# Logic_board.net
KiCad netlist of a schematic drawn in EAGLE
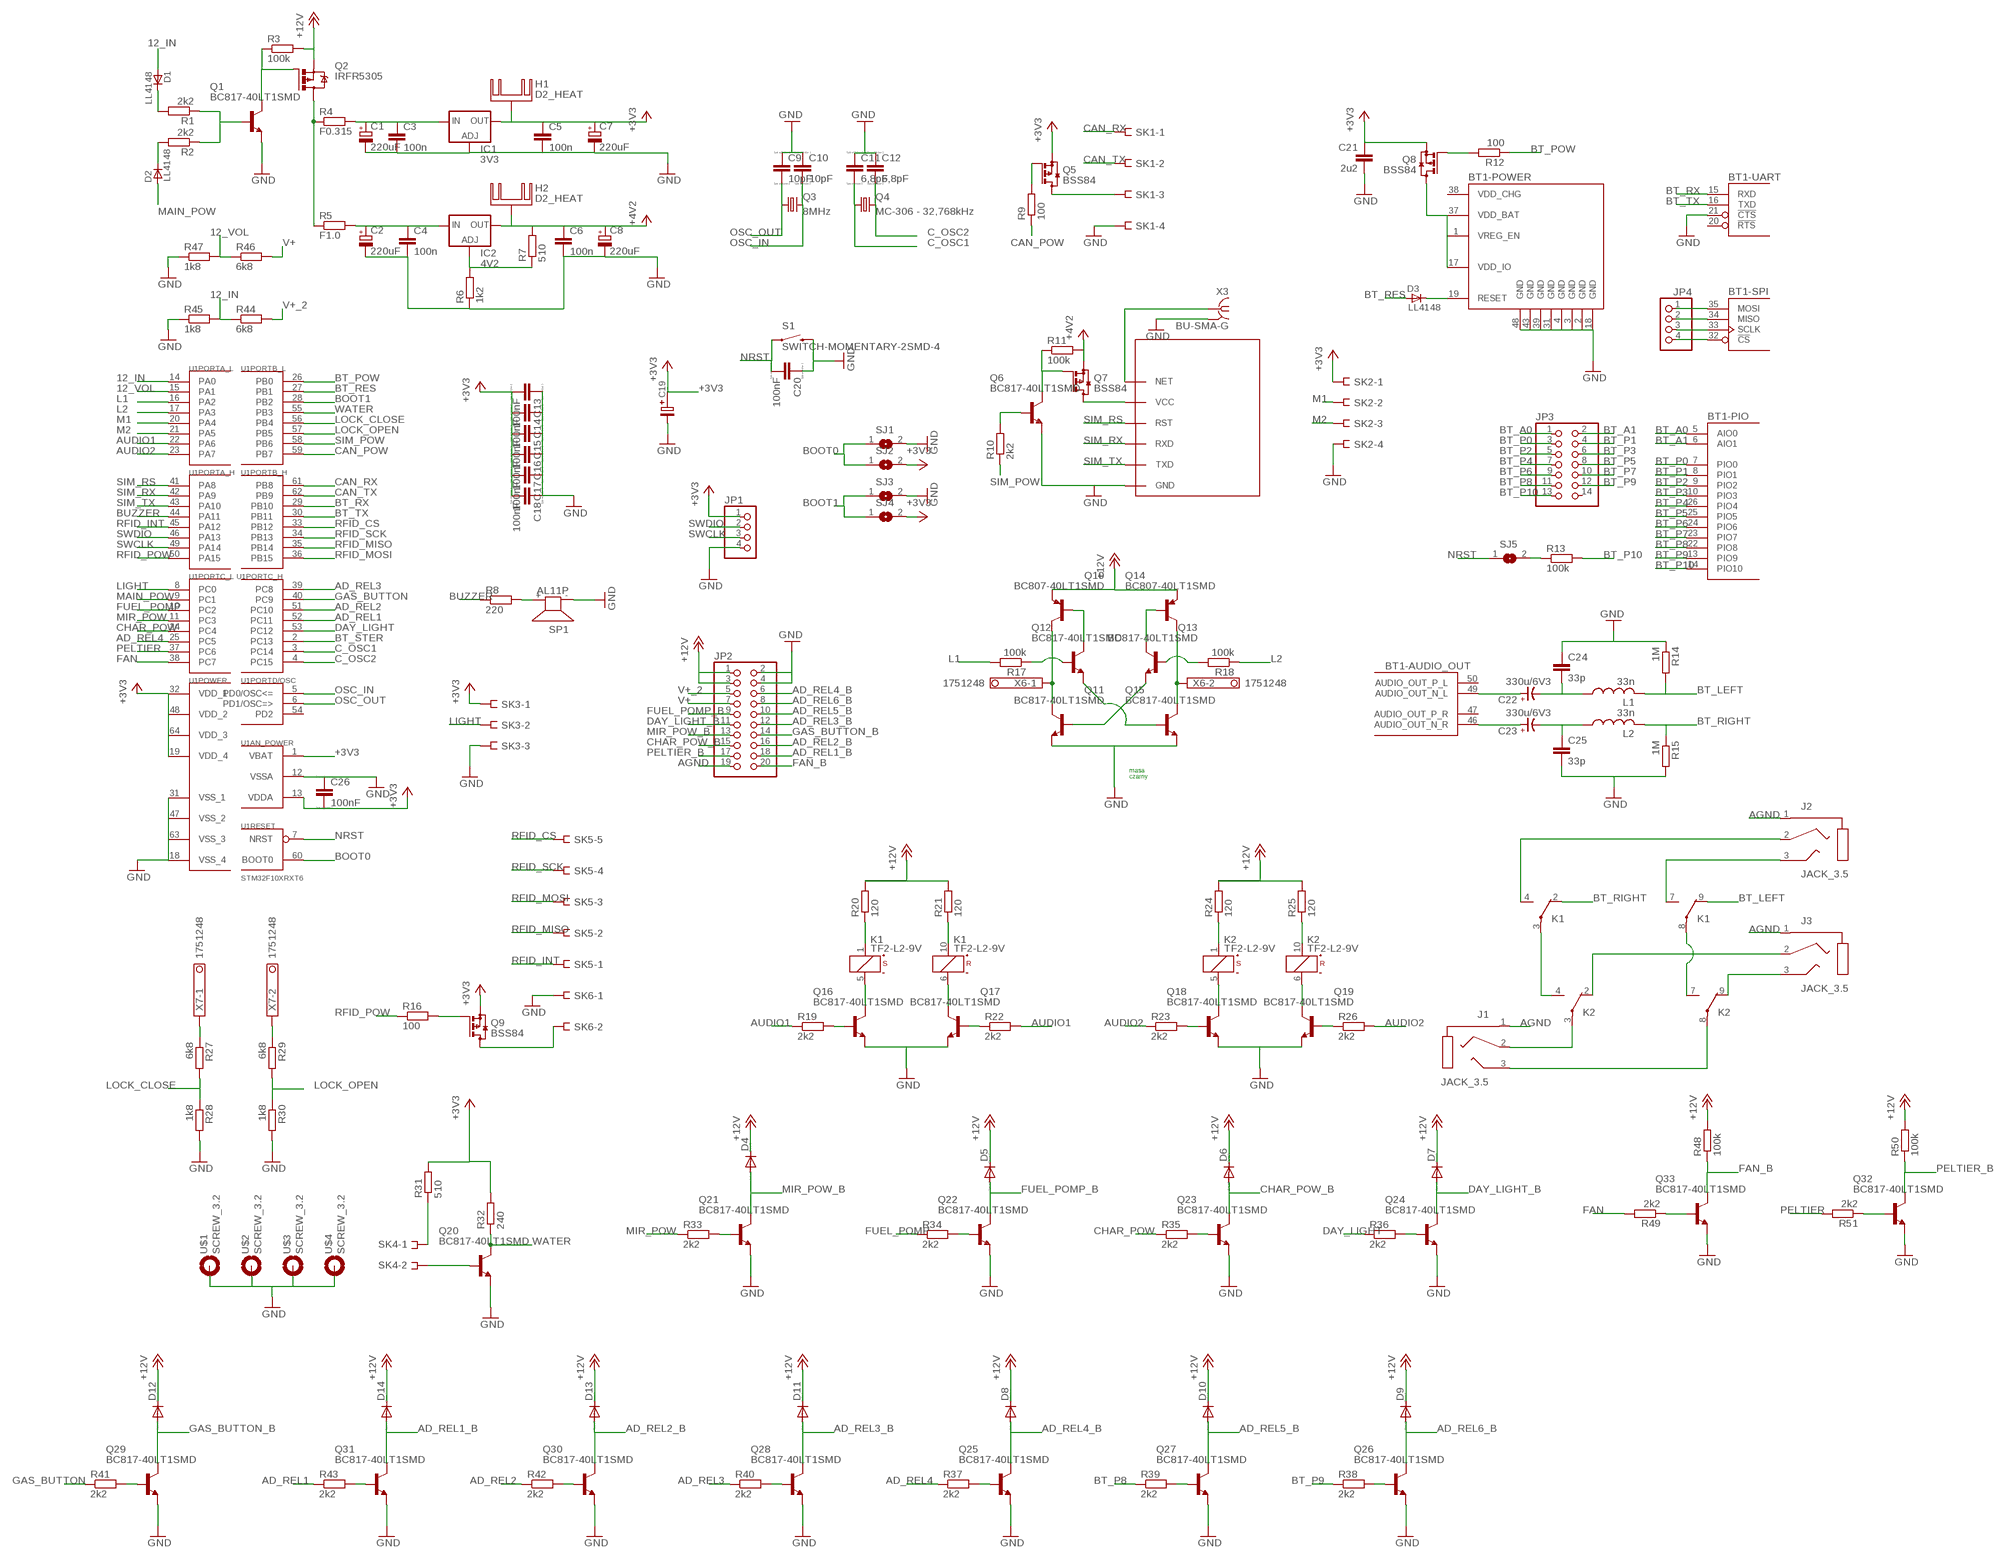
[diagram p0: schematic, sheet 1]

(export (version "E")
  (design (tool "Eeschema 10.0.6"))
  (components
    (comp (ref "BT1")
      (value "WT32I")
      (footprint "eagle-import:WT32I")
      (libsource (lib "eagle-import") (part "WT32I"))
    )
    (comp (ref "C1")
      (value "220uF")
      (footprint "eagle-import:PANASONIC_D")
      (libsource (lib "eagle-import") (part "CPOL-EUD"))
    )
    (comp (ref "C2")
      (value "220uF")
      (footprint "eagle-import:PANASONIC_D")
      (libsource (lib "eagle-import") (part "CPOL-EUD"))
    )
    (comp (ref "C3")
      (value "100n")
      (footprint "eagle-import:C2012")
      (libsource (lib "eagle-import") (part "C-EUC2012"))
    )
    (comp (ref "C4")
      (value "100n")
      (footprint "eagle-import:C2012")
      (libsource (lib "eagle-import") (part "C-EUC2012"))
    )
    (comp (ref "C5")
      (value "100n")
      (footprint "eagle-import:C2012")
      (libsource (lib "eagle-import") (part "C-EUC2012"))
    )
    (comp (ref "C6")
      (value "100n")
      (footprint "eagle-import:C2012")
      (libsource (lib "eagle-import") (part "C-EUC2012"))
    )
    (comp (ref "C7")
      (value "220uF")
      (footprint "eagle-import:PANASONIC_D")
      (libsource (lib "eagle-import") (part "CPOL-EUD"))
    )
    (comp (ref "C8")
      (value "220uF")
      (footprint "eagle-import:PANASONIC_D")
      (libsource (lib "eagle-import") (part "CPOL-EUD"))
    )
    (comp (ref "C9")
      (value "10pF")
      (footprint "eagle-import:C2012")
      (libsource (lib "eagle-import") (part "CC2012"))
    )
    (comp (ref "C10")
      (value "10pF")
      (footprint "eagle-import:C2012")
      (libsource (lib "eagle-import") (part "CC2012"))
    )
    (comp (ref "C11")
      (value "6,8pF")
      (footprint "eagle-import:C2012")
      (libsource (lib "eagle-import") (part "CC2012"))
    )
    (comp (ref "C12")
      (value "6,8pF")
      (footprint "eagle-import:C2012")
      (libsource (lib "eagle-import") (part "CC2012"))
    )
    (comp (ref "C13")
      (value "100nF")
      (footprint "eagle-import:C2012")
      (libsource (lib "eagle-import") (part "CC2012"))
    )
    (comp (ref "C14")
      (value "100nF")
      (footprint "eagle-import:C2012")
      (libsource (lib "eagle-import") (part "CC2012"))
    )
    (comp (ref "C15")
      (value "100nF")
      (footprint "eagle-import:C2012")
      (libsource (lib "eagle-import") (part "CC2012"))
    )
    (comp (ref "C16")
      (value "100nF")
      (footprint "eagle-import:C2012")
      (libsource (lib "eagle-import") (part "CC2012"))
    )
    (comp (ref "C17")
      (value "100nF")
      (footprint "eagle-import:C2012")
      (libsource (lib "eagle-import") (part "CC2012"))
    )
    (comp (ref "C18")
      (value "100nF")
      (footprint "eagle-import:C2012")
      (libsource (lib "eagle-import") (part "CC2012"))
    )
    (comp (ref "C19")
      (value "CAP-13,5")
      (footprint "eagle-import:PAC-G-1")
      (libsource (lib "eagle-import") (part "CAP-13,5"))
    )
    (comp (ref "C20")
      (value "100nF")
      (footprint "eagle-import:C2012")
      (libsource (lib "eagle-import") (part "CC2012"))
    )
    (comp (ref "C21")
      (value "2u2")
      (footprint "eagle-import:C2012")
      (libsource (lib "eagle-import") (part "C-EUC2012"))
    )
    (comp (ref "C22")
      (value "330u/6V3")
      (footprint "eagle-import:7343_T")
      (libsource (lib "eagle-import") (part "CP-7343"))
    )
    (comp (ref "C23")
      (value "330u/6V3")
      (footprint "eagle-import:7343_T")
      (libsource (lib "eagle-import") (part "CP-7343"))
    )
    (comp (ref "C24")
      (value "33p")
      (footprint "eagle-import:C2012")
      (libsource (lib "eagle-import") (part "C-EUC2012"))
    )
    (comp (ref "C25")
      (value "33p")
      (footprint "eagle-import:C2012")
      (libsource (lib "eagle-import") (part "C-EUC2012"))
    )
    (comp (ref "C26")
      (value "100nF")
      (footprint "eagle-import:C2012")
      (libsource (lib "eagle-import") (part "CC2012"))
    )
    (comp (ref "D1")
      (value "LL4148")
      (footprint "eagle-import:SOD80_DO213AA_MINIMELF")
      (libsource (lib "eagle-import") (part "LL4148"))
    )
    (comp (ref "D2")
      (value "LL4148")
      (footprint "eagle-import:SOD80_DO213AA_MINIMELF")
      (libsource (lib "eagle-import") (part "LL4148"))
    )
    (comp (ref "D3")
      (value "LL4148")
      (footprint "eagle-import:SOD80_DO213AA_MINIMELF")
      (libsource (lib "eagle-import") (part "LL4148"))
    )
    (comp (ref "D4")
      (value "DIODE-DO-214AC")
      (footprint "eagle-import:DO-214AC")
      (libsource (lib "eagle-import") (part "DIODE-DO-214AC"))
    )
    (comp (ref "D5")
      (value "DIODE-DO-214AC")
      (footprint "eagle-import:DO-214AC")
      (libsource (lib "eagle-import") (part "DIODE-DO-214AC"))
    )
    (comp (ref "D6")
      (value "DIODE-DO-214AC")
      (footprint "eagle-import:DO-214AC")
      (libsource (lib "eagle-import") (part "DIODE-DO-214AC"))
    )
    (comp (ref "D7")
      (value "DIODE-DO-214AC")
      (footprint "eagle-import:DO-214AC")
      (libsource (lib "eagle-import") (part "DIODE-DO-214AC"))
    )
    (comp (ref "D8")
      (value "DIODE-DO-214AC")
      (footprint "eagle-import:DO-214AC")
      (libsource (lib "eagle-import") (part "DIODE-DO-214AC"))
    )
    (comp (ref "D9")
      (value "DIODE-DO-214AC")
      (footprint "eagle-import:DO-214AC")
      (libsource (lib "eagle-import") (part "DIODE-DO-214AC"))
    )
    (comp (ref "D10")
      (value "DIODE-DO-214AC")
      (footprint "eagle-import:DO-214AC")
      (libsource (lib "eagle-import") (part "DIODE-DO-214AC"))
    )
    (comp (ref "D11")
      (value "DIODE-DO-214AC")
      (footprint "eagle-import:DO-214AC")
      (libsource (lib "eagle-import") (part "DIODE-DO-214AC"))
    )
    (comp (ref "D12")
      (value "DIODE-DO-214AC")
      (footprint "eagle-import:DO-214AC")
      (libsource (lib "eagle-import") (part "DIODE-DO-214AC"))
    )
    (comp (ref "D13")
      (value "DIODE-DO-214AC")
      (footprint "eagle-import:DO-214AC")
      (libsource (lib "eagle-import") (part "DIODE-DO-214AC"))
    )
    (comp (ref "D14")
      (value "DIODE-DO-214AC")
      (footprint "eagle-import:DO-214AC")
      (libsource (lib "eagle-import") (part "DIODE-DO-214AC"))
    )
    (comp (ref "H1")
      (value "D2_HEAT")
      (footprint "eagle-import:D2PACK_HEATSINK")
      (libsource (lib "eagle-import") (part "D2_HEAT"))
    )
    (comp (ref "H2")
      (value "D2_HEAT")
      (footprint "eagle-import:D2PACK_HEATSINK")
      (libsource (lib "eagle-import") (part "D2_HEAT"))
    )
    (comp (ref "IC1")
      (value "3V3")
      (footprint "eagle-import:D2PACK")
      (libsource (lib "eagle-import") (part "LM317?BD2T"))
    )
    (comp (ref "IC2")
      (value "4V2")
      (footprint "eagle-import:D2PACK")
      (libsource (lib "eagle-import") (part "LM317?BD2T"))
    )
    (comp (ref "J1")
      (value "JACK_3.5")
      (footprint "eagle-import:STX3100")
      (libsource (lib "eagle-import") (part "JACK_3.5"))
    )
    (comp (ref "J2")
      (value "JACK_3.5")
      (footprint "eagle-import:STX3100")
      (libsource (lib "eagle-import") (part "JACK_3.5"))
    )
    (comp (ref "J3")
      (value "JACK_3.5")
      (footprint "eagle-import:STX3100")
      (libsource (lib "eagle-import") (part "JACK_3.5"))
    )
    (comp (ref "JP1")
      (value "PINHD-1X4")
      (footprint "eagle-import:1X04")
      (libsource (lib "eagle-import") (part "PINHD-1X4"))
    )
    (comp (ref "JP2")
      (value "PINHD-2X10")
      (footprint "eagle-import:2X10")
      (libsource (lib "eagle-import") (part "PINHD-2X10"))
    )
    (comp (ref "JP3")
      (value "PINHD-2X7")
      (footprint "eagle-import:2X07")
      (libsource (lib "eagle-import") (part "PINHD-2X7"))
    )
    (comp (ref "JP4")
      (value "PINHD-1X4")
      (footprint "eagle-import:1X04")
      (libsource (lib "eagle-import") (part "PINHD-1X4"))
    )
    (comp (ref "K1")
      (value "TF2-L2-9V")
      (footprint "eagle-import:TF2")
      (libsource (lib "eagle-import") (part "TF2-L2-9V"))
    )
    (comp (ref "K2")
      (value "TF2-L2-9V")
      (footprint "eagle-import:TF2")
      (libsource (lib "eagle-import") (part "TF2-L2-9V"))
    )
    (comp (ref "L1")
      (value "33n")
      (footprint "eagle-import:L2012C")
      (libsource (lib "eagle-import") (part "L-USL2012C"))
    )
    (comp (ref "L2")
      (value "33n")
      (footprint "eagle-import:L2012C")
      (libsource (lib "eagle-import") (part "L-USL2012C"))
    )
    (comp (ref "Q1")
      (value "BC817-40LT1SMD")
      (footprint "eagle-import:SOT23-BEC")
      (libsource (lib "eagle-import") (part "BC817SMD-40LT1"))
    )
    (comp (ref "Q2")
      (value "IRFR5305")
      (footprint "eagle-import:D-PAK_TO252AA")
      (libsource (lib "eagle-import") (part "IRF?5305R"))
    )
    (comp (ref "Q3")
      (value "8MHz")
      (footprint "eagle-import:HC49UP")
      (libsource (lib "eagle-import") (part "CRYSTALHC49UP"))
    )
    (comp (ref "Q4")
      (value "MC-306 - 32,768kHz")
      (footprint "eagle-import:MC-306")
      (fields (field (name "MPN") "MC-306 60.0KHZ  100PPM ,12.5PF"))
      (libsource (lib "eagle-import") (part "MC-306"))
    )
    (comp (ref "Q5")
      (value "BSS84")
      (footprint "eagle-import:SOT23")
      (libsource (lib "eagle-import") (part "BSS84"))
    )
    (comp (ref "Q6")
      (value "BC817-40LT1SMD")
      (footprint "eagle-import:SOT23-BEC")
      (libsource (lib "eagle-import") (part "BC817SMD-40LT1"))
    )
    (comp (ref "Q7")
      (value "BSS84")
      (footprint "eagle-import:SOT23")
      (libsource (lib "eagle-import") (part "BSS84"))
    )
    (comp (ref "Q8")
      (value "BSS84")
      (footprint "eagle-import:SOT23")
      (libsource (lib "eagle-import") (part "BSS84"))
    )
    (comp (ref "Q9")
      (value "BSS84")
      (footprint "eagle-import:SOT23")
      (libsource (lib "eagle-import") (part "BSS84"))
    )
    (comp (ref "Q10")
      (value "BC807-40LT1SMD")
      (footprint "eagle-import:SOT23-BEC")
      (libsource (lib "eagle-import") (part "BC807SMD-40LT1"))
    )
    (comp (ref "Q11")
      (value "BC817-40LT1SMD")
      (footprint "eagle-import:SOT23-BEC")
      (libsource (lib "eagle-import") (part "BC817SMD-40LT1"))
    )
    (comp (ref "Q12")
      (value "BC817-40LT1SMD")
      (footprint "eagle-import:SOT23-BEC")
      (libsource (lib "eagle-import") (part "BC817SMD-40LT1"))
    )
    (comp (ref "Q13")
      (value "BC817-40LT1SMD")
      (footprint "eagle-import:SOT23-BEC")
      (libsource (lib "eagle-import") (part "BC817SMD-40LT1"))
    )
    (comp (ref "Q14")
      (value "BC807-40LT1SMD")
      (footprint "eagle-import:SOT23-BEC")
      (libsource (lib "eagle-import") (part "BC807SMD-40LT1"))
    )
    (comp (ref "Q15")
      (value "BC817-40LT1SMD")
      (footprint "eagle-import:SOT23-BEC")
      (libsource (lib "eagle-import") (part "BC817SMD-40LT1"))
    )
    (comp (ref "Q16")
      (value "BC817-40LT1SMD")
      (footprint "eagle-import:SOT23-BEC")
      (libsource (lib "eagle-import") (part "BC817SMD-40LT1"))
    )
    (comp (ref "Q17")
      (value "BC817-40LT1SMD")
      (footprint "eagle-import:SOT23-BEC")
      (libsource (lib "eagle-import") (part "BC817SMD-40LT1"))
    )
    (comp (ref "Q18")
      (value "BC817-40LT1SMD")
      (footprint "eagle-import:SOT23-BEC")
      (libsource (lib "eagle-import") (part "BC817SMD-40LT1"))
    )
    (comp (ref "Q19")
      (value "BC817-40LT1SMD")
      (footprint "eagle-import:SOT23-BEC")
      (libsource (lib "eagle-import") (part "BC817SMD-40LT1"))
    )
    (comp (ref "Q20")
      (value "BC817-40LT1SMD")
      (footprint "eagle-import:SOT23-BEC")
      (libsource (lib "eagle-import") (part "BC817SMD-40LT1"))
    )
    (comp (ref "Q21")
      (value "BC817-40LT1SMD")
      (footprint "eagle-import:SOT23-BEC")
      (libsource (lib "eagle-import") (part "BC817SMD-40LT1"))
    )
    (comp (ref "Q22")
      (value "BC817-40LT1SMD")
      (footprint "eagle-import:SOT23-BEC")
      (libsource (lib "eagle-import") (part "BC817SMD-40LT1"))
    )
    (comp (ref "Q23")
      (value "BC817-40LT1SMD")
      (footprint "eagle-import:SOT23-BEC")
      (libsource (lib "eagle-import") (part "BC817SMD-40LT1"))
    )
    (comp (ref "Q24")
      (value "BC817-40LT1SMD")
      (footprint "eagle-import:SOT23-BEC")
      (libsource (lib "eagle-import") (part "BC817SMD-40LT1"))
    )
    (comp (ref "Q25")
      (value "BC817-40LT1SMD")
      (footprint "eagle-import:SOT23-BEC")
      (libsource (lib "eagle-import") (part "BC817SMD-40LT1"))
    )
    (comp (ref "Q26")
      (value "BC817-40LT1SMD")
      (footprint "eagle-import:SOT23-BEC")
      (libsource (lib "eagle-import") (part "BC817SMD-40LT1"))
    )
    (comp (ref "Q27")
      (value "BC817-40LT1SMD")
      (footprint "eagle-import:SOT23-BEC")
      (libsource (lib "eagle-import") (part "BC817SMD-40LT1"))
    )
    (comp (ref "Q28")
      (value "BC817-40LT1SMD")
      (footprint "eagle-import:SOT23-BEC")
      (libsource (lib "eagle-import") (part "BC817SMD-40LT1"))
    )
    (comp (ref "Q29")
      (value "BC817-40LT1SMD")
      (footprint "eagle-import:SOT23-BEC")
      (libsource (lib "eagle-import") (part "BC817SMD-40LT1"))
    )
    (comp (ref "Q30")
      (value "BC817-40LT1SMD")
      (footprint "eagle-import:SOT23-BEC")
      (libsource (lib "eagle-import") (part "BC817SMD-40LT1"))
    )
    (comp (ref "Q31")
      (value "BC817-40LT1SMD")
      (footprint "eagle-import:SOT23-BEC")
      (libsource (lib "eagle-import") (part "BC817SMD-40LT1"))
    )
    (comp (ref "Q32")
      (value "BC817-40LT1SMD")
      (footprint "eagle-import:SOT23-BEC")
      (libsource (lib "eagle-import") (part "BC817SMD-40LT1"))
    )
    (comp (ref "Q33")
      (value "BC817-40LT1SMD")
      (footprint "eagle-import:SOT23-BEC")
      (libsource (lib "eagle-import") (part "BC817SMD-40LT1"))
    )
    (comp (ref "R1")
      (value "2k2")
      (footprint "eagle-import:R0805")
      (libsource (lib "eagle-import") (part "R-EU_R0805"))
    )
    (comp (ref "R2")
      (value "2k2")
      (footprint "eagle-import:R0805")
      (libsource (lib "eagle-import") (part "R-EU_R0805"))
    )
    (comp (ref "R3")
      (value "100k")
      (footprint "eagle-import:R0805")
      (libsource (lib "eagle-import") (part "R-EU_R0805"))
    )
    (comp (ref "R4")
      (value "F0.315")
      (footprint "eagle-import:R2512")
      (libsource (lib "eagle-import") (part "R-EU_R2512"))
    )
    (comp (ref "R5")
      (value "F1.0")
      (footprint "eagle-import:R2512")
      (libsource (lib "eagle-import") (part "R-EU_R2512"))
    )
    (comp (ref "R6")
      (value "1k2")
      (footprint "eagle-import:R0805")
      (libsource (lib "eagle-import") (part "R-EU_R0805"))
    )
    (comp (ref "R7")
      (value "510")
      (footprint "eagle-import:R0805")
      (libsource (lib "eagle-import") (part "R-EU_R0805"))
    )
    (comp (ref "R8")
      (value "220")
      (footprint "eagle-import:R0805")
      (libsource (lib "eagle-import") (part "R-EU_R0805"))
    )
    (comp (ref "R9")
      (value "100")
      (footprint "eagle-import:R0805")
      (libsource (lib "eagle-import") (part "R-EU_R0805"))
    )
    (comp (ref "R10")
      (value "2k2")
      (footprint "eagle-import:R0805")
      (libsource (lib "eagle-import") (part "R-EU_R0805"))
    )
    (comp (ref "R11")
      (value "100k")
      (footprint "eagle-import:R0805")
      (libsource (lib "eagle-import") (part "R-EU_R0805"))
    )
    (comp (ref "R12")
      (value "100")
      (footprint "eagle-import:R0805")
      (libsource (lib "eagle-import") (part "R-EU_R0805"))
    )
    (comp (ref "R13")
      (value "100k")
      (footprint "eagle-import:R0805")
      (libsource (lib "eagle-import") (part "R-EU_R0805"))
    )
    (comp (ref "R14")
      (value "1M")
      (footprint "eagle-import:R0805")
      (libsource (lib "eagle-import") (part "R-EU_R0805"))
    )
    (comp (ref "R15")
      (value "1M")
      (footprint "eagle-import:R0805")
      (libsource (lib "eagle-import") (part "R-EU_R0805"))
    )
    (comp (ref "R16")
      (value "100")
      (footprint "eagle-import:R0805")
      (libsource (lib "eagle-import") (part "R-EU_R0805"))
    )
    (comp (ref "R17")
      (value "100k")
      (footprint "eagle-import:R0805")
      (libsource (lib "eagle-import") (part "R-EU_R0805"))
    )
    (comp (ref "R18")
      (value "100k")
      (footprint "eagle-import:R0805")
      (libsource (lib "eagle-import") (part "R-EU_R0805"))
    )
    (comp (ref "R19")
      (value "2k2")
      (footprint "eagle-import:R0805")
      (libsource (lib "eagle-import") (part "R-EU_R0805"))
    )
    (comp (ref "R20")
      (value "120")
      (footprint "eagle-import:R0805")
      (libsource (lib "eagle-import") (part "R-EU_R0805"))
    )
    (comp (ref "R21")
      (value "120")
      (footprint "eagle-import:R0805")
      (libsource (lib "eagle-import") (part "R-EU_R0805"))
    )
    (comp (ref "R22")
      (value "2k2")
      (footprint "eagle-import:R0805")
      (libsource (lib "eagle-import") (part "R-EU_R0805"))
    )
    (comp (ref "R23")
      (value "2k2")
      (footprint "eagle-import:R0805")
      (libsource (lib "eagle-import") (part "R-EU_R0805"))
    )
    (comp (ref "R24")
      (value "120")
      (footprint "eagle-import:R0805")
      (libsource (lib "eagle-import") (part "R-EU_R0805"))
    )
    (comp (ref "R25")
      (value "120")
      (footprint "eagle-import:R0805")
      (libsource (lib "eagle-import") (part "R-EU_R0805"))
    )
    (comp (ref "R26")
      (value "2k2")
      (footprint "eagle-import:R0805")
      (libsource (lib "eagle-import") (part "R-EU_R0805"))
    )
    (comp (ref "R27")
      (value "6k8")
      (footprint "eagle-import:R0805")
      (libsource (lib "eagle-import") (part "R-EU_R0805"))
    )
    (comp (ref "R28")
      (value "1k8")
      (footprint "eagle-import:R0805")
      (libsource (lib "eagle-import") (part "R-EU_R0805"))
    )
    (comp (ref "R29")
      (value "6k8")
      (footprint "eagle-import:R0805")
      (libsource (lib "eagle-import") (part "R-EU_R0805"))
    )
    (comp (ref "R30")
      (value "1k8")
      (footprint "eagle-import:R0805")
      (libsource (lib "eagle-import") (part "R-EU_R0805"))
    )
    (comp (ref "R31")
      (value "510")
      (footprint "eagle-import:R0805")
      (libsource (lib "eagle-import") (part "R-EU_R0805"))
    )
    (comp (ref "R32")
      (value "240")
      (footprint "eagle-import:R0805")
      (libsource (lib "eagle-import") (part "R-EU_R0805"))
    )
    (comp (ref "R33")
      (value "2k2")
      (footprint "eagle-import:R0805")
      (libsource (lib "eagle-import") (part "R-EU_R0805"))
    )
    (comp (ref "R34")
      (value "2k2")
      (footprint "eagle-import:R0805")
      (libsource (lib "eagle-import") (part "R-EU_R0805"))
    )
    (comp (ref "R35")
      (value "2k2")
      (footprint "eagle-import:R0805")
      (libsource (lib "eagle-import") (part "R-EU_R0805"))
    )
    (comp (ref "R36")
      (value "2k2")
      (footprint "eagle-import:R0805")
      (libsource (lib "eagle-import") (part "R-EU_R0805"))
    )
    (comp (ref "R37")
      (value "2k2")
      (footprint "eagle-import:R0805")
      (libsource (lib "eagle-import") (part "R-EU_R0805"))
    )
    (comp (ref "R38")
      (value "2k2")
      (footprint "eagle-import:R0805")
      (libsource (lib "eagle-import") (part "R-EU_R0805"))
    )
    (comp (ref "R39")
      (value "2k2")
      (footprint "eagle-import:R0805")
      (libsource (lib "eagle-import") (part "R-EU_R0805"))
    )
    (comp (ref "R40")
      (value "2k2")
      (footprint "eagle-import:R0805")
      (libsource (lib "eagle-import") (part "R-EU_R0805"))
    )
    (comp (ref "R41")
      (value "2k2")
      (footprint "eagle-import:R0805")
      (libsource (lib "eagle-import") (part "R-EU_R0805"))
    )
    (comp (ref "R42")
      (value "2k2")
      (footprint "eagle-import:R0805")
      (libsource (lib "eagle-import") (part "R-EU_R0805"))
    )
    (comp (ref "R43")
      (value "2k2")
      (footprint "eagle-import:R0805")
      (libsource (lib "eagle-import") (part "R-EU_R0805"))
    )
    (comp (ref "R44")
      (value "6k8")
      (footprint "eagle-import:R0805")
      (libsource (lib "eagle-import") (part "R-EU_R0805"))
    )
    (comp (ref "R45")
      (value "1k8")
      (footprint "eagle-import:R0805")
      (libsource (lib "eagle-import") (part "R-EU_R0805"))
    )
    (comp (ref "R46")
      (value "6k8")
      (footprint "eagle-import:R0805")
      (libsource (lib "eagle-import") (part "R-EU_R0805"))
    )
    (comp (ref "R47")
      (value "1k8")
      (footprint "eagle-import:R0805")
      (libsource (lib "eagle-import") (part "R-EU_R0805"))
    )
    (comp (ref "R48")
      (value "100k")
      (footprint "eagle-import:R0805")
      (libsource (lib "eagle-import") (part "R-EU_R0805"))
    )
    (comp (ref "R49")
      (value "2k2")
      (footprint "eagle-import:R0805")
      (libsource (lib "eagle-import") (part "R-EU_R0805"))
    )
    (comp (ref "R50")
      (value "100k")
      (footprint "eagle-import:R0805")
      (libsource (lib "eagle-import") (part "R-EU_R0805"))
    )
    (comp (ref "R51")
      (value "2k2")
      (footprint "eagle-import:R0805")
      (libsource (lib "eagle-import") (part "R-EU_R0805"))
    )
    (comp (ref "S1")
      (value "SWITCH-MOMENTARY-2SMD-4")
      (footprint "eagle-import:TACTILE_SWITCH_TALL")
      (libsource (lib "eagle-import") (part "SWITCH-MOMENTARY-2SMD-4"))
    )
    (comp (ref "SJ1") (value "SJ") (footprint "eagle-import:SJ") (libsource (lib "eagle-import") (part "SJ")))
    (comp (ref "SJ2") (value "SJ") (footprint "eagle-import:SJ") (libsource (lib "eagle-import") (part "SJ")))
    (comp (ref "SJ3") (value "SJ") (footprint "eagle-import:SJ") (libsource (lib "eagle-import") (part "SJ")))
    (comp (ref "SJ4") (value "SJ") (footprint "eagle-import:SJ") (libsource (lib "eagle-import") (part "SJ")))
    (comp (ref "SJ5") (value "SJ") (footprint "eagle-import:SJ") (libsource (lib "eagle-import") (part "SJ")))
    (comp (ref "SK1")
      (value "DF3-04S")
      (footprint "eagle-import:DF3S-04")
      (libsource (lib "eagle-import") (part "DF3-04S"))
    )
    (comp (ref "SK2")
      (value "DF3-04S")
      (footprint "eagle-import:DF3S-04")
      (libsource (lib "eagle-import") (part "DF3-04S"))
    )
    (comp (ref "SK3")
      (value "DF3-03S")
      (footprint "eagle-import:DF3S-03")
      (libsource (lib "eagle-import") (part "DF3-03S"))
    )
    (comp (ref "SK4")
      (value "DF3-02S")
      (footprint "eagle-import:DF3S-02")
      (libsource (lib "eagle-import") (part "DF3-02S"))
    )
    (comp (ref "SK5")
      (value "DF3-05S")
      (footprint "eagle-import:DF3S-05")
      (libsource (lib "eagle-import") (part "DF3-05S"))
    )
    (comp (ref "SK6")
      (value "DF3-02S")
      (footprint "eagle-import:DF3S-02")
      (libsource (lib "eagle-import") (part "DF3-02S"))
    )
    (comp (ref "SP1")
      (value "AL11P")
      (footprint "eagle-import:AL11P")
      (libsource (lib "eagle-import") (part "AL11P"))
    )
    (comp (ref "U$1")
      (value "SCREW_3.2")
      (footprint "eagle-import:3,2-PAD")
      (libsource (lib "eagle-import") (part "SCREW_3.2"))
    )
    (comp (ref "U$2")
      (value "SCREW_3.2")
      (footprint "eagle-import:3,2-PAD")
      (libsource (lib "eagle-import") (part "SCREW_3.2"))
    )
    (comp (ref "U$3")
      (value "SCREW_3.2")
      (footprint "eagle-import:3,2-PAD")
      (libsource (lib "eagle-import") (part "SCREW_3.2"))
    )
    (comp (ref "U$4")
      (value "SCREW_3.2")
      (footprint "eagle-import:3,2-PAD")
      (libsource (lib "eagle-import") (part "SCREW_3.2"))
    )
    (comp (ref "U1")
      (value "STM32F10XRXT6")
      (footprint "eagle-import:TQFP64")
      (libsource (lib "eagle-import") (part "STM32F10XRXT6"))
    )
    (comp (ref "U2")
      (value "SIM800L")
      (footprint "eagle-import:SIM-CORE")
      (libsource (lib "eagle-import") (part "SIM800L"))
    )
    (comp (ref "X3")
      (value "BU-SMA-G")
      (footprint "eagle-import:BU-SMA-G")
      (libsource (lib "eagle-import") (part "BU-SMA-G"))
    )
    (comp (ref "X6")
      (value "1751248")
      (footprint "eagle-import:1751248")
      (libsource (lib "eagle-import") (part "1751248"))
    )
    (comp (ref "X7")
      (value "1751248")
      (footprint "eagle-import:1751248")
      (libsource (lib "eagle-import") (part "1751248"))
    )
  )
  (nets
    (net (code "1") (name "+3V3") (class "Default")
      (node (ref "C13") (pin "2") (pinfunction "2_2") (pintype "passive"))
      (node (ref "C14") (pin "2") (pinfunction "2_2") (pintype "passive"))
      (node (ref "C15") (pin "2") (pinfunction "2_2") (pintype "passive"))
      (node (ref "C16") (pin "2") (pinfunction "2_2") (pintype "passive"))
      (node (ref "C17") (pin "2") (pinfunction "2_2") (pintype "passive"))
      (node (ref "C18") (pin "2") (pinfunction "2_2") (pintype "passive"))
      (node (ref "C19") (pin "+") (pinfunction "+_+") (pintype "passive"))
      (node (ref "C21") (pin "1") (pinfunction "1_1") (pintype "passive"))
      (node (ref "C26") (pin "2") (pinfunction "2_2") (pintype "passive"))
      (node (ref "C5") (pin "1") (pinfunction "1_1") (pintype "passive"))
      (node (ref "C7") (pin "+") (pinfunction "+_+") (pintype "passive"))
      (node (ref "H1") (pin "1") (pinfunction "K_1") (pintype "passive"))
      (node (ref "IC1") (pin "2") (pinfunction "OUT_2") (pintype "passive"))
      (node (ref "JP1") (pin "1") (pinfunction "1_1") (pintype "passive"))
      (node (ref "Q5") (pin "2") (pinfunction "S_2") (pintype "passive"))
      (node (ref "Q8") (pin "2") (pinfunction "S_2") (pintype "passive"))
      (node (ref "Q9") (pin "2") (pinfunction "S_2") (pintype "passive"))
      (node (ref "R31") (pin "2") (pinfunction "2_2") (pintype "passive"))
      (node (ref "R32") (pin "2") (pinfunction "2_2") (pintype "passive"))
      (node (ref "SJ2") (pin "2") (pinfunction "2_2") (pintype "passive"))
      (node (ref "SJ4") (pin "2") (pinfunction "2_2") (pintype "passive"))
      (node (ref "SK2") (pin "1") (pinfunction "S_1") (pintype "passive"))
      (node (ref "SK3") (pin "1") (pinfunction "S_1") (pintype "passive"))
      (node (ref "U1") (pin "1") (pinfunction "VBAT_1") (pintype "power_in"))
      (node (ref "U1") (pin "13") (pinfunction "VDDA_13") (pintype "power_in"))
      (node (ref "U1") (pin "19") (pinfunction "VDD_4_19") (pintype "power_in"))
      (node (ref "U1") (pin "32") (pinfunction "VDD_1_32") (pintype "power_in"))
      (node (ref "U1") (pin "48") (pinfunction "VDD_2_48") (pintype "power_in"))
      (node (ref "U1") (pin "64") (pinfunction "VDD_3_64") (pintype "power_in"))
    )
    (net (code "2") (name "+4V2") (class "Default")
      (node (ref "C6") (pin "1") (pinfunction "1_1") (pintype "passive"))
      (node (ref "C8") (pin "+") (pinfunction "+_+") (pintype "passive"))
      (node (ref "H2") (pin "1") (pinfunction "K_1") (pintype "passive"))
      (node (ref "IC2") (pin "2") (pinfunction "OUT_2") (pintype "passive"))
      (node (ref "Q7") (pin "2") (pinfunction "S_2") (pintype "passive"))
      (node (ref "R11") (pin "2") (pinfunction "2_2") (pintype "passive"))
      (node (ref "R7") (pin "2") (pinfunction "2_2") (pintype "passive"))
    )
    (net (code "3") (name "+12V") (class "Default")
      (node (ref "D10") (pin "C") (pinfunction "C_C") (pintype "passive"))
      (node (ref "D11") (pin "C") (pinfunction "C_C") (pintype "passive"))
      (node (ref "D12") (pin "C") (pinfunction "C_C") (pintype "passive"))
      (node (ref "D13") (pin "C") (pinfunction "C_C") (pintype "passive"))
      (node (ref "D14") (pin "C") (pinfunction "C_C") (pintype "passive"))
      (node (ref "D4") (pin "C") (pinfunction "C_C") (pintype "passive"))
      (node (ref "D5") (pin "C") (pinfunction "C_C") (pintype "passive"))
      (node (ref "D6") (pin "C") (pinfunction "C_C") (pintype "passive"))
      (node (ref "D7") (pin "C") (pinfunction "C_C") (pintype "passive"))
      (node (ref "D8") (pin "C") (pinfunction "C_C") (pintype "passive"))
      (node (ref "D9") (pin "C") (pinfunction "C_C") (pintype "passive"))
      (node (ref "JP2") (pin "1") (pinfunction "1_1") (pintype "passive"))
      (node (ref "JP2") (pin "3") (pinfunction "3_3") (pintype "passive"))
      (node (ref "Q10") (pin "E") (pinfunction "E_E") (pintype "passive"))
      (node (ref "Q14") (pin "E") (pinfunction "E_E") (pintype "passive"))
      (node (ref "Q2") (pin "3") (pinfunction "S_3") (pintype "passive"))
      (node (ref "R20") (pin "2") (pinfunction "2_2") (pintype "passive"))
      (node (ref "R21") (pin "2") (pinfunction "2_2") (pintype "passive"))
      (node (ref "R24") (pin "2") (pinfunction "2_2") (pintype "passive"))
      (node (ref "R25") (pin "2") (pinfunction "2_2") (pintype "passive"))
      (node (ref "R3") (pin "2") (pinfunction "2_2") (pintype "passive"))
      (node (ref "R48") (pin "2") (pinfunction "2_2") (pintype "passive"))
      (node (ref "R50") (pin "2") (pinfunction "2_2") (pintype "passive"))
    )
    (net (code "4") (name "/12_IN") (class "Default")
      (node (ref "D1") (pin "A") (pinfunction "A_A") (pintype "passive"))
      (node (ref "R44") (pin "1") (pinfunction "1_1") (pintype "passive"))
      (node (ref "R45") (pin "2") (pinfunction "2_2") (pintype "passive"))
      (node (ref "U1") (pin "14") (pinfunction "PA0_14") (pintype "bidirectional"))
    )
    (net (code "5") (name "/12_VOL") (class "Default")
      (node (ref "R46") (pin "1") (pinfunction "1_1") (pintype "passive"))
      (node (ref "R47") (pin "2") (pinfunction "2_2") (pintype "passive"))
      (node (ref "U1") (pin "15") (pinfunction "PA1_15") (pintype "bidirectional"))
    )
    (net (code "6") (name "/AD_REL1") (class "Default")
      (node (ref "R43") (pin "1") (pinfunction "1_1") (pintype "passive"))
      (node (ref "U1") (pin "52") (pinfunction "PC11_52") (pintype "bidirectional"))
    )
    (net (code "7") (name "/AD_REL1_B") (class "Default")
      (node (ref "D14") (pin "A") (pinfunction "A_A") (pintype "passive"))
      (node (ref "JP2") (pin "18") (pinfunction "18_18") (pintype "passive"))
      (node (ref "Q31") (pin "C") (pinfunction "C_C") (pintype "passive"))
    )
    (net (code "8") (name "/AD_REL2") (class "Default")
      (node (ref "R42") (pin "1") (pinfunction "1_1") (pintype "passive"))
      (node (ref "U1") (pin "51") (pinfunction "PC10_51") (pintype "bidirectional"))
    )
    (net (code "9") (name "/AD_REL2_B") (class "Default")
      (node (ref "D13") (pin "A") (pinfunction "A_A") (pintype "passive"))
      (node (ref "JP2") (pin "16") (pinfunction "16_16") (pintype "passive"))
      (node (ref "Q30") (pin "C") (pinfunction "C_C") (pintype "passive"))
    )
    (net (code "10") (name "/AD_REL3") (class "Default")
      (node (ref "R40") (pin "1") (pinfunction "1_1") (pintype "passive"))
      (node (ref "U1") (pin "39") (pinfunction "PC8_39") (pintype "bidirectional"))
    )
    (net (code "11") (name "/AD_REL3_B") (class "Default")
      (node (ref "D11") (pin "A") (pinfunction "A_A") (pintype "passive"))
      (node (ref "JP2") (pin "12") (pinfunction "12_12") (pintype "passive"))
      (node (ref "Q28") (pin "C") (pinfunction "C_C") (pintype "passive"))
    )
    (net (code "12") (name "/AD_REL4") (class "Default")
      (node (ref "R37") (pin "1") (pinfunction "1_1") (pintype "passive"))
      (node (ref "U1") (pin "25") (pinfunction "PC5_25") (pintype "bidirectional"))
    )
    (net (code "13") (name "/AD_REL4_B") (class "Default")
      (node (ref "D8") (pin "A") (pinfunction "A_A") (pintype "passive"))
      (node (ref "JP2") (pin "6") (pinfunction "6_6") (pintype "passive"))
      (node (ref "Q25") (pin "C") (pinfunction "C_C") (pintype "passive"))
    )
    (net (code "14") (name "/AD_REL5_B") (class "Default")
      (node (ref "D10") (pin "A") (pinfunction "A_A") (pintype "passive"))
      (node (ref "JP2") (pin "10") (pinfunction "10_10") (pintype "passive"))
      (node (ref "Q27") (pin "C") (pinfunction "C_C") (pintype "passive"))
    )
    (net (code "15") (name "/AD_REL6_B") (class "Default")
      (node (ref "D9") (pin "A") (pinfunction "A_A") (pintype "passive"))
      (node (ref "JP2") (pin "8") (pinfunction "8_8") (pintype "passive"))
      (node (ref "Q26") (pin "C") (pinfunction "C_C") (pintype "passive"))
    )
    (net (code "16") (name "/AGND") (class "Default")
      (node (ref "J1") (pin "1") (pinfunction "1_1") (pintype "passive"))
      (node (ref "J2") (pin "1") (pinfunction "1_1") (pintype "passive"))
      (node (ref "J3") (pin "1") (pinfunction "1_1") (pintype "passive"))
      (node (ref "JP2") (pin "19") (pinfunction "19_19") (pintype "passive"))
    )
    (net (code "17") (name "/AUDIO1") (class "Default")
      (node (ref "R19") (pin "1") (pinfunction "1_1") (pintype "passive"))
      (node (ref "R22") (pin "2") (pinfunction "2_2") (pintype "passive"))
      (node (ref "U1") (pin "22") (pinfunction "PA6_22") (pintype "bidirectional"))
    )
    (net (code "18") (name "/AUDIO2") (class "Default")
      (node (ref "R23") (pin "1") (pinfunction "1_1") (pintype "passive"))
      (node (ref "R26") (pin "2") (pinfunction "2_2") (pintype "passive"))
      (node (ref "U1") (pin "23") (pinfunction "PA7_23") (pintype "bidirectional"))
    )
    (net (code "19") (name "/BOOT0") (class "Default")
      (node (ref "SJ1") (pin "1") (pinfunction "1_1") (pintype "passive"))
      (node (ref "SJ2") (pin "1") (pinfunction "1_1") (pintype "passive"))
      (node (ref "U1") (pin "60") (pinfunction "BOOT0_60") (pintype "input"))
    )
    (net (code "20") (name "/BOOT1") (class "Default")
      (node (ref "SJ3") (pin "1") (pinfunction "1_1") (pintype "passive"))
      (node (ref "SJ4") (pin "1") (pinfunction "1_1") (pintype "passive"))
      (node (ref "U1") (pin "28") (pinfunction "PB2_28") (pintype "bidirectional"))
    )
    (net (code "21") (name "/BT_A0") (class "Default")
      (node (ref "BT1") (pin "5") (pinfunction "AIO0_5") (pintype "bidirectional"))
      (node (ref "JP3") (pin "1") (pinfunction "1_1") (pintype "passive"))
    )
    (net (code "22") (name "/BT_A1") (class "Default")
      (node (ref "BT1") (pin "6") (pinfunction "AIO1_6") (pintype "bidirectional"))
      (node (ref "JP3") (pin "2") (pinfunction "2_2") (pintype "passive"))
    )
    (net (code "23") (name "/BT_LEFT") (class "Default")
      (node (ref "K1") (pin "9") (pinfunction "O_9") (pintype "passive"))
      (node (ref "L1") (pin "2") (pinfunction "2_2") (pintype "passive"))
      (node (ref "R14") (pin "2") (pinfunction "2_2") (pintype "passive"))
    )
    (net (code "24") (name "/BT_P0") (class "Default")
      (node (ref "BT1") (pin "7") (pinfunction "PIO0_7") (pintype "bidirectional"))
      (node (ref "JP3") (pin "3") (pinfunction "3_3") (pintype "passive"))
    )
    (net (code "25") (name "/BT_P1") (class "Default")
      (node (ref "BT1") (pin "8") (pinfunction "PIO1_8") (pintype "bidirectional"))
      (node (ref "JP3") (pin "4") (pinfunction "4_4") (pintype "passive"))
    )
    (net (code "26") (name "/BT_P2") (class "Default")
      (node (ref "BT1") (pin "9") (pinfunction "PIO2_9") (pintype "bidirectional"))
      (node (ref "JP3") (pin "5") (pinfunction "5_5") (pintype "passive"))
    )
    (net (code "27") (name "/BT_P3") (class "Default")
      (node (ref "BT1") (pin "10") (pinfunction "PIO3_10") (pintype "bidirectional"))
      (node (ref "JP3") (pin "6") (pinfunction "6_6") (pintype "passive"))
    )
    (net (code "28") (name "/BT_P4") (class "Default")
      (node (ref "BT1") (pin "26") (pinfunction "PIO4_26") (pintype "bidirectional"))
      (node (ref "JP3") (pin "7") (pinfunction "7_7") (pintype "passive"))
    )
    (net (code "29") (name "/BT_P5") (class "Default")
      (node (ref "BT1") (pin "25") (pinfunction "PIO5_25") (pintype "bidirectional"))
      (node (ref "JP3") (pin "8") (pinfunction "8_8") (pintype "passive"))
    )
    (net (code "30") (name "/BT_P6") (class "Default")
      (node (ref "BT1") (pin "24") (pinfunction "PIO6_24") (pintype "bidirectional"))
      (node (ref "JP3") (pin "9") (pinfunction "9_9") (pintype "passive"))
    )
    (net (code "31") (name "/BT_P7") (class "Default")
      (node (ref "BT1") (pin "23") (pinfunction "PIO7_23") (pintype "bidirectional"))
      (node (ref "JP3") (pin "10") (pinfunction "10_10") (pintype "passive"))
    )
    (net (code "32") (name "/BT_P8") (class "Default")
      (node (ref "BT1") (pin "22") (pinfunction "PIO8_22") (pintype "bidirectional"))
      (node (ref "JP3") (pin "11") (pinfunction "11_11") (pintype "passive"))
      (node (ref "R39") (pin "1") (pinfunction "1_1") (pintype "passive"))
    )
    (net (code "33") (name "/BT_P9") (class "Default")
      (node (ref "BT1") (pin "13") (pinfunction "PIO9_13") (pintype "bidirectional"))
      (node (ref "JP3") (pin "12") (pinfunction "12_12") (pintype "passive"))
      (node (ref "R38") (pin "1") (pinfunction "1_1") (pintype "passive"))
    )
    (net (code "34") (name "/BT_P10") (class "Default")
      (node (ref "BT1") (pin "14") (pinfunction "PIO10_14") (pintype "bidirectional"))
      (node (ref "JP3") (pin "13") (pinfunction "13_13") (pintype "passive"))
      (node (ref "R13") (pin "2") (pinfunction "2_2") (pintype "passive"))
    )
    (net (code "35") (name "/BT_POW") (class "Default")
      (node (ref "R12") (pin "1") (pinfunction "1_1") (pintype "passive"))
      (node (ref "U1") (pin "26") (pinfunction "PB0_26") (pintype "bidirectional"))
    )
    (net (code "36") (name "/BT_RES") (class "Default")
      (node (ref "D3") (pin "A") (pinfunction "A_A") (pintype "passive"))
      (node (ref "U1") (pin "27") (pinfunction "PB1_27") (pintype "bidirectional"))
    )
    (net (code "37") (name "/BT_RIGHT") (class "Default")
      (node (ref "K1") (pin "2") (pinfunction "O_2") (pintype "passive"))
      (node (ref "L2") (pin "2") (pinfunction "2_2") (pintype "passive"))
      (node (ref "R15") (pin "1") (pinfunction "1_1") (pintype "passive"))
    )
    (net (code "38") (name "/BT_RX") (class "Default")
      (node (ref "BT1") (pin "15") (pinfunction "RXD_15") (pintype "input"))
      (node (ref "U1") (pin "29") (pinfunction "PB10_29") (pintype "bidirectional"))
    )
    (net (code "39") (name "/BT_STER") (class "Default")
      (node (ref "U1") (pin "2") (pinfunction "PC13_2") (pintype "bidirectional"))
    )
    (net (code "40") (name "/BT_TX") (class "Default")
      (node (ref "BT1") (pin "16") (pinfunction "TXD_16") (pintype "output"))
      (node (ref "U1") (pin "30") (pinfunction "PB11_30") (pintype "bidirectional"))
    )
    (net (code "41") (name "/BUZZER") (class "Default")
      (node (ref "R8") (pin "1") (pinfunction "1_1") (pintype "passive"))
      (node (ref "U1") (pin "44") (pinfunction "PA11_44") (pintype "bidirectional"))
    )
    (net (code "42") (name "/CAN_POW") (class "Default")
      (node (ref "R9") (pin "1") (pinfunction "1_1") (pintype "passive"))
      (node (ref "U1") (pin "59") (pinfunction "PB7_59") (pintype "bidirectional"))
    )
    (net (code "43") (name "/CAN_RX") (class "Default")
      (node (ref "SK1") (pin "1") (pinfunction "S_1") (pintype "passive"))
      (node (ref "U1") (pin "61") (pinfunction "PB8_61") (pintype "bidirectional"))
    )
    (net (code "44") (name "/CAN_TX") (class "Default")
      (node (ref "SK1") (pin "2") (pinfunction "S_2") (pintype "passive"))
      (node (ref "U1") (pin "62") (pinfunction "PB9_62") (pintype "bidirectional"))
    )
    (net (code "45") (name "/CHAR_POW") (class "Default")
      (node (ref "R35") (pin "1") (pinfunction "1_1") (pintype "passive"))
      (node (ref "U1") (pin "24") (pinfunction "PC4_24") (pintype "bidirectional"))
    )
    (net (code "46") (name "/CHAR_POW_B") (class "Default")
      (node (ref "D6") (pin "A") (pinfunction "A_A") (pintype "passive"))
      (node (ref "JP2") (pin "15") (pinfunction "15_15") (pintype "passive"))
      (node (ref "Q23") (pin "C") (pinfunction "C_C") (pintype "passive"))
    )
    (net (code "47") (name "/C_OSC1") (class "Default")
      (node (ref "C11") (pin "2") (pinfunction "2_2") (pintype "passive"))
      (node (ref "Q4") (pin "1") (pinfunction "1_1") (pintype "passive"))
      (node (ref "U1") (pin "3") (pinfunction "PC14_3") (pintype "bidirectional"))
    )
    (net (code "48") (name "/C_OSC2") (class "Default")
      (node (ref "C12") (pin "2") (pinfunction "2_2") (pintype "passive"))
      (node (ref "Q4") (pin "4") (pinfunction "2_4") (pintype "passive"))
      (node (ref "U1") (pin "4") (pinfunction "PC15_4") (pintype "bidirectional"))
    )
    (net (code "49") (name "/DAY_LIGHT") (class "Default")
      (node (ref "R36") (pin "1") (pinfunction "1_1") (pintype "passive"))
      (node (ref "U1") (pin "53") (pinfunction "PC12_53") (pintype "bidirectional"))
    )
    (net (code "50") (name "/DAY_LIGHT_B") (class "Default")
      (node (ref "D7") (pin "A") (pinfunction "A_A") (pintype "passive"))
      (node (ref "JP2") (pin "11") (pinfunction "11_11") (pintype "passive"))
      (node (ref "Q24") (pin "C") (pinfunction "C_C") (pintype "passive"))
    )
    (net (code "51") (name "/FAN") (class "Default")
      (node (ref "R49") (pin "2") (pinfunction "2_2") (pintype "passive"))
      (node (ref "U1") (pin "38") (pinfunction "PC7_38") (pintype "bidirectional"))
    )
    (net (code "52") (name "/FAN_B") (class "Default")
      (node (ref "JP2") (pin "20") (pinfunction "20_20") (pintype "passive"))
      (node (ref "Q33") (pin "C") (pinfunction "C_C") (pintype "passive"))
      (node (ref "R48") (pin "1") (pinfunction "1_1") (pintype "passive"))
    )
    (net (code "53") (name "/FUEL_POMP") (class "Default")
      (node (ref "R34") (pin "1") (pinfunction "1_1") (pintype "passive"))
      (node (ref "U1") (pin "10") (pinfunction "PC2_10") (pintype "bidirectional"))
    )
    (net (code "54") (name "/FUEL_POMP_B") (class "Default")
      (node (ref "D5") (pin "A") (pinfunction "A_A") (pintype "passive"))
      (node (ref "JP2") (pin "9") (pinfunction "9_9") (pintype "passive"))
      (node (ref "Q22") (pin "C") (pinfunction "C_C") (pintype "passive"))
    )
    (net (code "55") (name "/GAS_BUTTON") (class "Default")
      (node (ref "R41") (pin "1") (pinfunction "1_1") (pintype "passive"))
      (node (ref "U1") (pin "40") (pinfunction "PC9_40") (pintype "bidirectional"))
    )
    (net (code "56") (name "/GAS_BUTTON_B") (class "Default")
      (node (ref "D12") (pin "A") (pinfunction "A_A") (pintype "passive"))
      (node (ref "JP2") (pin "14") (pinfunction "14_14") (pintype "passive"))
      (node (ref "Q29") (pin "C") (pinfunction "C_C") (pintype "passive"))
    )
    (net (code "57") (name "/L1") (class "Default")
      (node (ref "R17") (pin "2") (pinfunction "2_2") (pintype "passive"))
      (node (ref "U1") (pin "16") (pinfunction "PA2_16") (pintype "bidirectional"))
    )
    (net (code "58") (name "/L2") (class "Default")
      (node (ref "R18") (pin "1") (pinfunction "1_1") (pintype "passive"))
      (node (ref "U1") (pin "17") (pinfunction "PA3_17") (pintype "bidirectional"))
    )
    (net (code "59") (name "/LIGHT") (class "Default")
      (node (ref "SK3") (pin "2") (pinfunction "S_2") (pintype "passive"))
      (node (ref "U1") (pin "8") (pinfunction "PC0_8") (pintype "bidirectional"))
    )
    (net (code "60") (name "/LOCK_CLOSE") (class "Default")
      (node (ref "R27") (pin "2") (pinfunction "2_2") (pintype "passive"))
      (node (ref "R28") (pin "1") (pinfunction "1_1") (pintype "passive"))
      (node (ref "U1") (pin "56") (pinfunction "PB4_56") (pintype "bidirectional"))
    )
    (net (code "61") (name "/LOCK_OPEN") (class "Default")
      (node (ref "R29") (pin "2") (pinfunction "2_2") (pintype "passive"))
      (node (ref "R30") (pin "1") (pinfunction "1_1") (pintype "passive"))
      (node (ref "U1") (pin "57") (pinfunction "PB5_57") (pintype "bidirectional"))
    )
    (net (code "62") (name "/M1") (class "Default")
      (node (ref "SK2") (pin "2") (pinfunction "S_2") (pintype "passive"))
      (node (ref "U1") (pin "20") (pinfunction "PA4_20") (pintype "bidirectional"))
    )
    (net (code "63") (name "/M2") (class "Default")
      (node (ref "SK2") (pin "3") (pinfunction "S_3") (pintype "passive"))
      (node (ref "U1") (pin "21") (pinfunction "PA5_21") (pintype "bidirectional"))
    )
    (net (code "64") (name "/MAIN_POW") (class "Default")
      (node (ref "D2") (pin "A") (pinfunction "A_A") (pintype "passive"))
      (node (ref "U1") (pin "9") (pinfunction "PC1_9") (pintype "bidirectional"))
    )
    (net (code "65") (name "/MIR_POW") (class "Default")
      (node (ref "R33") (pin "1") (pinfunction "1_1") (pintype "passive"))
      (node (ref "U1") (pin "11") (pinfunction "PC3_11") (pintype "bidirectional"))
    )
    (net (code "66") (name "/MIR_POW_B") (class "Default")
      (node (ref "D4") (pin "A") (pinfunction "A_A") (pintype "passive"))
      (node (ref "JP2") (pin "13") (pinfunction "13_13") (pintype "passive"))
      (node (ref "Q21") (pin "C") (pinfunction "C_C") (pintype "passive"))
    )
    (net (code "67") (name "/NRST") (class "Default")
      (node (ref "C20") (pin "2") (pinfunction "2_2") (pintype "passive"))
      (node (ref "S1") (pin "A2") (pinfunction "1_A2") (pintype "passive"))
      (node (ref "SJ5") (pin "1") (pinfunction "1_1") (pintype "passive"))
      (node (ref "U1") (pin "7") (pinfunction "NRST_7") (pintype "input"))
    )
    (net (code "68") (name "/OSC_IN") (class "Default")
      (node (ref "C10") (pin "2") (pinfunction "2_2") (pintype "passive"))
      (node (ref "Q3") (pin "2") (pinfunction "2_2") (pintype "passive"))
      (node (ref "U1") (pin "5") (pinfunction "PD0/OSC<=_5") (pintype "bidirectional"))
    )
    (net (code "69") (name "/OSC_OUT") (class "Default")
      (node (ref "C9") (pin "2") (pinfunction "2_2") (pintype "passive"))
      (node (ref "Q3") (pin "1") (pinfunction "1_1") (pintype "passive"))
      (node (ref "U1") (pin "6") (pinfunction "PD1/OSC=>_6") (pintype "bidirectional"))
    )
    (net (code "70") (name "/PELTIER") (class "Default")
      (node (ref "R51") (pin "2") (pinfunction "2_2") (pintype "passive"))
      (node (ref "U1") (pin "37") (pinfunction "PC6_37") (pintype "bidirectional"))
    )
    (net (code "71") (name "/PELTIER_B") (class "Default")
      (node (ref "JP2") (pin "17") (pinfunction "17_17") (pintype "passive"))
      (node (ref "Q32") (pin "C") (pinfunction "C_C") (pintype "passive"))
      (node (ref "R50") (pin "1") (pinfunction "1_1") (pintype "passive"))
    )
    (net (code "72") (name "/RFID_CS") (class "Default")
      (node (ref "SK5") (pin "5") (pinfunction "S_5") (pintype "passive"))
      (node (ref "U1") (pin "33") (pinfunction "PB12_33") (pintype "bidirectional"))
    )
    (net (code "73") (name "/RFID_INT") (class "Default")
      (node (ref "SK5") (pin "1") (pinfunction "S_1") (pintype "passive"))
      (node (ref "U1") (pin "45") (pinfunction "PA12_45") (pintype "bidirectional"))
    )
    (net (code "74") (name "/RFID_MISO") (class "Default")
      (node (ref "SK5") (pin "2") (pinfunction "S_2") (pintype "passive"))
      (node (ref "U1") (pin "35") (pinfunction "PB14_35") (pintype "bidirectional"))
    )
    (net (code "75") (name "/RFID_MOSI") (class "Default")
      (node (ref "SK5") (pin "3") (pinfunction "S_3") (pintype "passive"))
      (node (ref "U1") (pin "36") (pinfunction "PB15_36") (pintype "bidirectional"))
    )
    (net (code "76") (name "/RFID_POW") (class "Default")
      (node (ref "R16") (pin "1") (pinfunction "1_1") (pintype "passive"))
      (node (ref "U1") (pin "50") (pinfunction "PA15_50") (pintype "bidirectional"))
    )
    (net (code "77") (name "/RFID_SCK") (class "Default")
      (node (ref "SK5") (pin "4") (pinfunction "S_4") (pintype "passive"))
      (node (ref "U1") (pin "34") (pinfunction "PB13_34") (pintype "bidirectional"))
    )
    (net (code "78") (name "/SIM_POW") (class "Default")
      (node (ref "R10") (pin "1") (pinfunction "1_1") (pintype "passive"))
      (node (ref "U1") (pin "58") (pinfunction "PB6_58") (pintype "bidirectional"))
    )
    (net (code "79") (name "/SIM_RS") (class "Default")
      (node (ref "U1") (pin "41") (pinfunction "PA8_41") (pintype "bidirectional"))
      (node (ref "U2") (pin "RST") (pinfunction "RST_RST") (pintype "bidirectional"))
    )
    (net (code "80") (name "/SIM_RX") (class "Default")
      (node (ref "U1") (pin "42") (pinfunction "PA9_42") (pintype "bidirectional"))
      (node (ref "U2") (pin "RXD") (pinfunction "RXD_RXD") (pintype "bidirectional"))
    )
    (net (code "81") (name "/SIM_TX") (class "Default")
      (node (ref "U1") (pin "43") (pinfunction "PA10_43") (pintype "bidirectional"))
      (node (ref "U2") (pin "TXD") (pinfunction "TXD_TXD") (pintype "bidirectional"))
    )
    (net (code "82") (name "/SWCLK") (class "Default")
      (node (ref "JP1") (pin "3") (pinfunction "3_3") (pintype "passive"))
      (node (ref "U1") (pin "49") (pinfunction "PA14_49") (pintype "bidirectional"))
    )
    (net (code "83") (name "/SWDIO") (class "Default")
      (node (ref "JP1") (pin "2") (pinfunction "2_2") (pintype "passive"))
      (node (ref "U1") (pin "46") (pinfunction "PA13_46") (pintype "bidirectional"))
    )
    (net (code "84") (name "/V+") (class "Default")
      (node (ref "JP2") (pin "7") (pinfunction "7_7") (pintype "passive"))
      (node (ref "R46") (pin "2") (pinfunction "2_2") (pintype "passive"))
    )
    (net (code "85") (name "/V+_2") (class "Default")
      (node (ref "JP2") (pin "5") (pinfunction "5_5") (pintype "passive"))
      (node (ref "R44") (pin "2") (pinfunction "2_2") (pintype "passive"))
    )
    (net (code "86") (name "/VDD_CHG") (class "Default")
      (node (ref "BT1") (pin "38") (pinfunction "VDD_CHG_38") (pintype "power_in"))
    )
    (net (code "87") (name "/WATER") (class "Default")
      (node (ref "Q20") (pin "C") (pinfunction "C_C") (pintype "passive"))
      (node (ref "R32") (pin "1") (pinfunction "1_1") (pintype "passive"))
      (node (ref "U1") (pin "55") (pinfunction "PB3_55") (pintype "bidirectional"))
    )
    (net (code "88") (name "GND") (class "Default")
      (node (ref "BT1") (pin "18") (pinfunction "GND_18") (pintype "passive"))
      (node (ref "BT1") (pin "2") (pinfunction "GND_2") (pintype "passive"))
      (node (ref "BT1") (pin "21") (pinfunction "~{CTS}_21") (pintype "input"))
      (node (ref "BT1") (pin "3") (pinfunction "GND_3") (pintype "passive"))
      (node (ref "BT1") (pin "31") (pinfunction "GND_31") (pintype "passive"))
      (node (ref "BT1") (pin "39") (pinfunction "GND_39") (pintype "passive"))
      (node (ref "BT1") (pin "4") (pinfunction "GND_4") (pintype "passive"))
      (node (ref "BT1") (pin "43") (pinfunction "GND_43") (pintype "passive"))
      (node (ref "BT1") (pin "48") (pinfunction "GND_48") (pintype "passive"))
      (node (ref "C1") (pin "-") (pinfunction "-_-") (pintype "passive"))
      (node (ref "C10") (pin "1") (pinfunction "1_1") (pintype "passive"))
      (node (ref "C11") (pin "1") (pinfunction "1_1") (pintype "passive"))
      (node (ref "C12") (pin "1") (pinfunction "1_1") (pintype "passive"))
      (node (ref "C13") (pin "1") (pinfunction "1_1") (pintype "passive"))
      (node (ref "C14") (pin "1") (pinfunction "1_1") (pintype "passive"))
      (node (ref "C15") (pin "1") (pinfunction "1_1") (pintype "passive"))
      (node (ref "C16") (pin "1") (pinfunction "1_1") (pintype "passive"))
      (node (ref "C17") (pin "1") (pinfunction "1_1") (pintype "passive"))
      (node (ref "C18") (pin "1") (pinfunction "1_1") (pintype "passive"))
      (node (ref "C19") (pin "-") (pinfunction "-_-") (pintype "passive"))
      (node (ref "C2") (pin "-") (pinfunction "-_-") (pintype "passive"))
      (node (ref "C20") (pin "1") (pinfunction "1_1") (pintype "passive"))
      (node (ref "C21") (pin "2") (pinfunction "2_2") (pintype "passive"))
      (node (ref "C24") (pin "1") (pinfunction "1_1") (pintype "passive"))
      (node (ref "C25") (pin "2") (pinfunction "2_2") (pintype "passive"))
      (node (ref "C26") (pin "1") (pinfunction "1_1") (pintype "passive"))
      (node (ref "C3") (pin "2") (pinfunction "2_2") (pintype "passive"))
      (node (ref "C4") (pin "2") (pinfunction "2_2") (pintype "passive"))
      (node (ref "C5") (pin "2") (pinfunction "2_2") (pintype "passive"))
      (node (ref "C6") (pin "2") (pinfunction "2_2") (pintype "passive"))
      (node (ref "C7") (pin "-") (pinfunction "-_-") (pintype "passive"))
      (node (ref "C8") (pin "-") (pinfunction "-_-") (pintype "passive"))
      (node (ref "C9") (pin "1") (pinfunction "1_1") (pintype "passive"))
      (node (ref "IC1") (pin "1") (pinfunction "ADJ_1") (pintype "input"))
      (node (ref "JP1") (pin "4") (pinfunction "4_4") (pintype "passive"))
      (node (ref "JP2") (pin "2") (pinfunction "2_2") (pintype "passive"))
      (node (ref "JP2") (pin "4") (pinfunction "4_4") (pintype "passive"))
      (node (ref "Q1") (pin "E") (pinfunction "E_E") (pintype "passive"))
      (node (ref "Q11") (pin "E") (pinfunction "E_E") (pintype "passive"))
      (node (ref "Q15") (pin "E") (pinfunction "E_E") (pintype "passive"))
      (node (ref "Q16") (pin "E") (pinfunction "E_E") (pintype "passive"))
      (node (ref "Q17") (pin "E") (pinfunction "E_E") (pintype "passive"))
      (node (ref "Q18") (pin "E") (pinfunction "E_E") (pintype "passive"))
      (node (ref "Q19") (pin "E") (pinfunction "E_E") (pintype "passive"))
      (node (ref "Q20") (pin "E") (pinfunction "E_E") (pintype "passive"))
      (node (ref "Q21") (pin "E") (pinfunction "E_E") (pintype "passive"))
      (node (ref "Q22") (pin "E") (pinfunction "E_E") (pintype "passive"))
      (node (ref "Q23") (pin "E") (pinfunction "E_E") (pintype "passive"))
      (node (ref "Q24") (pin "E") (pinfunction "E_E") (pintype "passive"))
      (node (ref "Q25") (pin "E") (pinfunction "E_E") (pintype "passive"))
      (node (ref "Q26") (pin "E") (pinfunction "E_E") (pintype "passive"))
      (node (ref "Q27") (pin "E") (pinfunction "E_E") (pintype "passive"))
      (node (ref "Q28") (pin "E") (pinfunction "E_E") (pintype "passive"))
      (node (ref "Q29") (pin "E") (pinfunction "E_E") (pintype "passive"))
      (node (ref "Q30") (pin "E") (pinfunction "E_E") (pintype "passive"))
      (node (ref "Q31") (pin "E") (pinfunction "E_E") (pintype "passive"))
      (node (ref "Q32") (pin "E") (pinfunction "E_E") (pintype "passive"))
      (node (ref "Q33") (pin "E") (pinfunction "E_E") (pintype "passive"))
      (node (ref "Q6") (pin "E") (pinfunction "E_E") (pintype "passive"))
      (node (ref "R14") (pin "1") (pinfunction "1_1") (pintype "passive"))
      (node (ref "R15") (pin "2") (pinfunction "2_2") (pintype "passive"))
      (node (ref "R28") (pin "2") (pinfunction "2_2") (pintype "passive"))
      (node (ref "R30") (pin "2") (pinfunction "2_2") (pintype "passive"))
      (node (ref "R45") (pin "1") (pinfunction "1_1") (pintype "passive"))
      (node (ref "R47") (pin "1") (pinfunction "1_1") (pintype "passive"))
      (node (ref "R6") (pin "1") (pinfunction "1_1") (pintype "passive"))
      (node (ref "S1") (pin "B2") (pinfunction "2_B2") (pintype "passive"))
      (node (ref "SJ1") (pin "2") (pinfunction "2_2") (pintype "passive"))
      (node (ref "SJ3") (pin "2") (pinfunction "2_2") (pintype "passive"))
      (node (ref "SK1") (pin "4") (pinfunction "S_4") (pintype "passive"))
      (node (ref "SK2") (pin "4") (pinfunction "S_4") (pintype "passive"))
      (node (ref "SK3") (pin "3") (pinfunction "S_3") (pintype "passive"))
      (node (ref "SK6") (pin "1") (pinfunction "S_1") (pintype "passive"))
      (node (ref "SP1") (pin "-") (pinfunction "1_-") (pintype "passive"))
      (node (ref "U$1") (pin "B3,2") (pinfunction "MOUNT_B3,2") (pintype "passive"))
      (node (ref "U$2") (pin "B3,2") (pinfunction "MOUNT_B3,2") (pintype "passive"))
      (node (ref "U$3") (pin "B3,2") (pinfunction "MOUNT_B3,2") (pintype "passive"))
      (node (ref "U$4") (pin "B3,2") (pinfunction "MOUNT_B3,2") (pintype "passive"))
      (node (ref "U1") (pin "12") (pinfunction "VSSA_12") (pintype "power_in"))
      (node (ref "U1") (pin "18") (pinfunction "VSS_4_18") (pintype "power_in"))
      (node (ref "U1") (pin "31") (pinfunction "VSS_1_31") (pintype "power_in"))
      (node (ref "U1") (pin "47") (pinfunction "VSS_2_47") (pintype "power_in"))
      (node (ref "U1") (pin "63") (pinfunction "VSS_3_63") (pintype "power_in"))
      (node (ref "U2") (pin "GND") (pinfunction "GND_GND") (pintype "bidirectional"))
      (node (ref "X3") (pin "2") (pinfunction "2_2") (pintype "passive"))
      (node (ref "X3") (pin "3") (pinfunction "2_3") (pintype "passive"))
      (node (ref "X3") (pin "4") (pinfunction "2_4") (pintype "passive"))
      (node (ref "X3") (pin "5") (pinfunction "2_5") (pintype "passive"))
    )
    (net (code "89") (name "Net-(BT1B-AUDIO_OUT_N_L)") (class "Default")
      (node (ref "BT1") (pin "49") (pinfunction "AUDIO_OUT_N_L_49") (pintype "output"))
      (node (ref "C22") (pin "+") (pinfunction "+_+") (pintype "passive"))
    )
    (net (code "90") (name "Net-(BT1B-AUDIO_OUT_N_R)") (class "Default")
      (node (ref "BT1") (pin "46") (pinfunction "AUDIO_OUT_N_R_46") (pintype "output"))
      (node (ref "C23") (pin "+") (pinfunction "+_+") (pintype "passive"))
    )
    (net (code "91") (name "Net-(BT1F-RESET)") (class "Default")
      (node (ref "BT1") (pin "19") (pinfunction "RESET_19") (pintype "input"))
      (node (ref "D3") (pin "C") (pinfunction "C_C") (pintype "passive"))
    )
    (net (code "92") (name "Net-(BT1F-VDD_BAT)") (class "Default")
      (node (ref "BT1") (pin "1") (pinfunction "VREG_EN_1") (pintype "input"))
      (node (ref "BT1") (pin "17") (pinfunction "VDD_IO_17") (pintype "power_in"))
      (node (ref "BT1") (pin "37") (pinfunction "VDD_BAT_37") (pintype "bidirectional"))
      (node (ref "Q8") (pin "3") (pinfunction "D_3") (pintype "passive"))
    )
    (net (code "93") (name "Net-(BT1G-MISO)") (class "Default")
      (node (ref "BT1") (pin "34") (pinfunction "MISO_34") (pintype "output"))
      (node (ref "JP4") (pin "2") (pinfunction "2_2") (pintype "passive"))
    )
    (net (code "94") (name "Net-(BT1G-MOSI)") (class "Default")
      (node (ref "BT1") (pin "35") (pinfunction "MOSI_35") (pintype "input"))
      (node (ref "JP4") (pin "1") (pinfunction "1_1") (pintype "passive"))
    )
    (net (code "95") (name "Net-(BT1G-SCLK)") (class "Default")
      (node (ref "BT1") (pin "33") (pinfunction "SCLK_33") (pintype "input"))
      (node (ref "JP4") (pin "3") (pinfunction "3_3") (pintype "passive"))
    )
    (net (code "96") (name "Net-(BT1G-~{CS})") (class "Default")
      (node (ref "BT1") (pin "32") (pinfunction "~{CS}_32") (pintype "input"))
      (node (ref "JP4") (pin "4") (pinfunction "4_4") (pintype "passive"))
    )
    (net (code "97") (name "Net-(C22-Pad-)") (class "Default")
      (node (ref "C22") (pin "-") (pinfunction "-_-") (pintype "passive"))
      (node (ref "C24") (pin "2") (pinfunction "2_2") (pintype "passive"))
      (node (ref "L1") (pin "1") (pinfunction "1_1") (pintype "passive"))
    )
    (net (code "98") (name "Net-(C23-Pad-)") (class "Default")
      (node (ref "C23") (pin "-") (pinfunction "-_-") (pintype "passive"))
      (node (ref "C25") (pin "1") (pinfunction "1_1") (pintype "passive"))
      (node (ref "L2") (pin "1") (pinfunction "1_1") (pintype "passive"))
    )
    (net (code "99") (name "Net-(D1-PadC)") (class "Default")
      (node (ref "D1") (pin "C") (pinfunction "C_C") (pintype "passive"))
      (node (ref "R1") (pin "2") (pinfunction "2_2") (pintype "passive"))
    )
    (net (code "100") (name "Net-(D2-PadC)") (class "Default")
      (node (ref "D2") (pin "C") (pinfunction "C_C") (pintype "passive"))
      (node (ref "R2") (pin "2") (pinfunction "2_2") (pintype "passive"))
    )
    (net (code "101") (name "Net-(IC1-IN)") (class "Default")
      (node (ref "C1") (pin "+") (pinfunction "+_+") (pintype "passive"))
      (node (ref "C3") (pin "1") (pinfunction "1_1") (pintype "passive"))
      (node (ref "IC1") (pin "3") (pinfunction "IN_3") (pintype "input"))
      (node (ref "R4") (pin "2") (pinfunction "2_2") (pintype "passive"))
    )
    (net (code "102") (name "Net-(IC2-ADJ)") (class "Default")
      (node (ref "IC2") (pin "1") (pinfunction "ADJ_1") (pintype "input"))
      (node (ref "R6") (pin "2") (pinfunction "2_2") (pintype "passive"))
      (node (ref "R7") (pin "1") (pinfunction "1_1") (pintype "passive"))
    )
    (net (code "103") (name "Net-(IC2-IN)") (class "Default")
      (node (ref "C2") (pin "+") (pinfunction "+_+") (pintype "passive"))
      (node (ref "C4") (pin "1") (pinfunction "1_1") (pintype "passive"))
      (node (ref "IC2") (pin "3") (pinfunction "IN_3") (pintype "input"))
      (node (ref "R5") (pin "2") (pinfunction "2_2") (pintype "passive"))
    )
    (net (code "104") (name "Net-(J1-5)") (class "Default")
      (node (ref "J1") (pin "3") (pinfunction "5_3") (pintype "passive"))
      (node (ref "K2") (pin "8") (pinfunction "P_8") (pintype "passive"))
    )
    (net (code "105") (name "Net-(J2-5)") (class "Default")
      (node (ref "J2") (pin "3") (pinfunction "5_3") (pintype "passive"))
      (node (ref "K1") (pin "7") (pinfunction "S_7") (pintype "passive"))
    )
    (net (code "106") (name "Net-(J3-5)") (class "Default")
      (node (ref "J3") (pin "3") (pinfunction "5_3") (pintype "passive"))
      (node (ref "K2") (pin "9") (pinfunction "O_9") (pintype "passive"))
    )
    (net (code "107") (name "Net-(K1A-P)") (class "Default")
      (node (ref "K1") (pin "3") (pinfunction "P_3") (pintype "passive"))
      (node (ref "K2") (pin "4") (pinfunction "S_4") (pintype "passive"))
    )
    (net (code "108") (name "Net-(K1A-S)") (class "Default")
      (node (ref "J2") (pin "2") (pinfunction "2_2") (pintype "passive"))
      (node (ref "K1") (pin "4") (pinfunction "S_4") (pintype "passive"))
    )
    (net (code "109") (name "Net-(K1B-P)") (class "Default")
      (node (ref "K1") (pin "8") (pinfunction "P_8") (pintype "passive"))
      (node (ref "K2") (pin "7") (pinfunction "S_7") (pintype "passive"))
    )
    (net (code "110") (name "Net-(K1C-+)") (class "Default")
      (node (ref "K1") (pin "10") (pinfunction "+_10") (pintype "passive"))
      (node (ref "R21") (pin "1") (pinfunction "1_1") (pintype "passive"))
    )
    (net (code "111") (name "Net-(K1C--)") (class "Default")
      (node (ref "K1") (pin "6") (pinfunction "-_6") (pintype "passive"))
      (node (ref "Q17") (pin "C") (pinfunction "C_C") (pintype "passive"))
    )
    (net (code "112") (name "Net-(K1D-+)") (class "Default")
      (node (ref "K1") (pin "1") (pinfunction "+_1") (pintype "passive"))
      (node (ref "R20") (pin "1") (pinfunction "1_1") (pintype "passive"))
    )
    (net (code "113") (name "Net-(K1D--)") (class "Default")
      (node (ref "K1") (pin "5") (pinfunction "-_5") (pintype "passive"))
      (node (ref "Q16") (pin "C") (pinfunction "C_C") (pintype "passive"))
    )
    (net (code "114") (name "Net-(K2A-O)") (class "Default")
      (node (ref "J3") (pin "2") (pinfunction "2_2") (pintype "passive"))
      (node (ref "K2") (pin "2") (pinfunction "O_2") (pintype "passive"))
    )
    (net (code "115") (name "Net-(K2A-P)") (class "Default")
      (node (ref "J1") (pin "2") (pinfunction "2_2") (pintype "passive"))
      (node (ref "K2") (pin "3") (pinfunction "P_3") (pintype "passive"))
    )
    (net (code "116") (name "Net-(K2C-+)") (class "Default")
      (node (ref "K2") (pin "10") (pinfunction "+_10") (pintype "passive"))
      (node (ref "R25") (pin "1") (pinfunction "1_1") (pintype "passive"))
    )
    (net (code "117") (name "Net-(K2C--)") (class "Default")
      (node (ref "K2") (pin "6") (pinfunction "-_6") (pintype "passive"))
      (node (ref "Q19") (pin "C") (pinfunction "C_C") (pintype "passive"))
    )
    (net (code "118") (name "Net-(K2D-+)") (class "Default")
      (node (ref "K2") (pin "1") (pinfunction "+_1") (pintype "passive"))
      (node (ref "R24") (pin "1") (pinfunction "1_1") (pintype "passive"))
    )
    (net (code "119") (name "Net-(K2D--)") (class "Default")
      (node (ref "K2") (pin "5") (pinfunction "-_5") (pintype "passive"))
      (node (ref "Q18") (pin "C") (pinfunction "C_C") (pintype "passive"))
    )
    (net (code "120") (name "Net-(Q1-PadB)") (class "Default")
      (node (ref "Q1") (pin "B") (pinfunction "B_B") (pintype "passive"))
      (node (ref "R1") (pin "1") (pinfunction "1_1") (pintype "passive"))
      (node (ref "R2") (pin "1") (pinfunction "1_1") (pintype "passive"))
    )
    (net (code "121") (name "Net-(Q2-D)") (class "Default")
      (node (ref "Q2") (pin "4") (pinfunction "D_4") (pintype "passive"))
      (node (ref "R4") (pin "1") (pinfunction "1_1") (pintype "passive"))
      (node (ref "R5") (pin "1") (pinfunction "1_1") (pintype "passive"))
    )
    (net (code "122") (name "Net-(Q2-G)") (class "Default")
      (node (ref "Q1") (pin "C") (pinfunction "C_C") (pintype "passive"))
      (node (ref "Q2") (pin "1") (pinfunction "G_1") (pintype "passive"))
      (node (ref "R3") (pin "1") (pinfunction "1_1") (pintype "passive"))
    )
    (net (code "123") (name "Net-(Q5-D)") (class "Default")
      (node (ref "Q5") (pin "3") (pinfunction "D_3") (pintype "passive"))
      (node (ref "SK1") (pin "3") (pinfunction "S_3") (pintype "passive"))
    )
    (net (code "124") (name "Net-(Q5-G)") (class "Default")
      (node (ref "Q5") (pin "1") (pinfunction "G_1") (pintype "passive"))
      (node (ref "R9") (pin "2") (pinfunction "2_2") (pintype "passive"))
    )
    (net (code "125") (name "Net-(Q6-PadB)") (class "Default")
      (node (ref "Q6") (pin "B") (pinfunction "B_B") (pintype "passive"))
      (node (ref "R10") (pin "2") (pinfunction "2_2") (pintype "passive"))
    )
    (net (code "126") (name "Net-(Q7-D)") (class "Default")
      (node (ref "Q7") (pin "3") (pinfunction "D_3") (pintype "passive"))
      (node (ref "U2") (pin "VCC") (pinfunction "VCC_VCC") (pintype "bidirectional"))
    )
    (net (code "127") (name "Net-(Q7-G)") (class "Default")
      (node (ref "Q6") (pin "C") (pinfunction "C_C") (pintype "passive"))
      (node (ref "Q7") (pin "1") (pinfunction "G_1") (pintype "passive"))
      (node (ref "R11") (pin "1") (pinfunction "1_1") (pintype "passive"))
    )
    (net (code "128") (name "Net-(Q8-G)") (class "Default")
      (node (ref "Q8") (pin "1") (pinfunction "G_1") (pintype "passive"))
      (node (ref "R12") (pin "2") (pinfunction "2_2") (pintype "passive"))
    )
    (net (code "129") (name "Net-(Q9-D)") (class "Default")
      (node (ref "Q9") (pin "3") (pinfunction "D_3") (pintype "passive"))
      (node (ref "SK6") (pin "2") (pinfunction "S_2") (pintype "passive"))
    )
    (net (code "130") (name "Net-(Q9-G)") (class "Default")
      (node (ref "Q9") (pin "1") (pinfunction "G_1") (pintype "passive"))
      (node (ref "R16") (pin "2") (pinfunction "2_2") (pintype "passive"))
    )
    (net (code "131") (name "Net-(Q10-PadB)") (class "Default")
      (node (ref "Q10") (pin "B") (pinfunction "B_B") (pintype "passive"))
      (node (ref "Q12") (pin "C") (pinfunction "C_C") (pintype "passive"))
    )
    (net (code "132") (name "Net-(Q11-PadB)") (class "Default")
      (node (ref "Q11") (pin "B") (pinfunction "B_B") (pintype "passive"))
      (node (ref "Q13") (pin "E") (pinfunction "E_E") (pintype "passive"))
    )
    (net (code "133") (name "Net-(Q12-PadB)") (class "Default")
      (node (ref "Q12") (pin "B") (pinfunction "B_B") (pintype "passive"))
      (node (ref "R17") (pin "1") (pinfunction "1_1") (pintype "passive"))
    )
    (net (code "134") (name "Net-(Q12-PadE)") (class "Default")
      (node (ref "Q12") (pin "E") (pinfunction "E_E") (pintype "passive"))
      (node (ref "Q15") (pin "B") (pinfunction "B_B") (pintype "passive"))
    )
    (net (code "135") (name "Net-(Q13-PadB)") (class "Default")
      (node (ref "Q13") (pin "B") (pinfunction "B_B") (pintype "passive"))
      (node (ref "R18") (pin "2") (pinfunction "2_2") (pintype "passive"))
    )
    (net (code "136") (name "Net-(Q13-PadC)") (class "Default")
      (node (ref "Q13") (pin "C") (pinfunction "C_C") (pintype "passive"))
      (node (ref "Q14") (pin "B") (pinfunction "B_B") (pintype "passive"))
    )
    (net (code "137") (name "Net-(Q16-PadB)") (class "Default")
      (node (ref "Q16") (pin "B") (pinfunction "B_B") (pintype "passive"))
      (node (ref "R19") (pin "2") (pinfunction "2_2") (pintype "passive"))
    )
    (net (code "138") (name "Net-(Q17-PadB)") (class "Default")
      (node (ref "Q17") (pin "B") (pinfunction "B_B") (pintype "passive"))
      (node (ref "R22") (pin "1") (pinfunction "1_1") (pintype "passive"))
    )
    (net (code "139") (name "Net-(Q18-PadB)") (class "Default")
      (node (ref "Q18") (pin "B") (pinfunction "B_B") (pintype "passive"))
      (node (ref "R23") (pin "2") (pinfunction "2_2") (pintype "passive"))
    )
    (net (code "140") (name "Net-(Q19-PadB)") (class "Default")
      (node (ref "Q19") (pin "B") (pinfunction "B_B") (pintype "passive"))
      (node (ref "R26") (pin "1") (pinfunction "1_1") (pintype "passive"))
    )
    (net (code "141") (name "Net-(Q21-PadB)") (class "Default")
      (node (ref "Q21") (pin "B") (pinfunction "B_B") (pintype "passive"))
      (node (ref "R33") (pin "2") (pinfunction "2_2") (pintype "passive"))
    )
    (net (code "142") (name "Net-(Q22-PadB)") (class "Default")
      (node (ref "Q22") (pin "B") (pinfunction "B_B") (pintype "passive"))
      (node (ref "R34") (pin "2") (pinfunction "2_2") (pintype "passive"))
    )
    (net (code "143") (name "Net-(Q23-PadB)") (class "Default")
      (node (ref "Q23") (pin "B") (pinfunction "B_B") (pintype "passive"))
      (node (ref "R35") (pin "2") (pinfunction "2_2") (pintype "passive"))
    )
    (net (code "144") (name "Net-(Q24-PadB)") (class "Default")
      (node (ref "Q24") (pin "B") (pinfunction "B_B") (pintype "passive"))
      (node (ref "R36") (pin "2") (pinfunction "2_2") (pintype "passive"))
    )
    (net (code "145") (name "Net-(Q25-PadB)") (class "Default")
      (node (ref "Q25") (pin "B") (pinfunction "B_B") (pintype "passive"))
      (node (ref "R37") (pin "2") (pinfunction "2_2") (pintype "passive"))
    )
    (net (code "146") (name "Net-(Q26-PadB)") (class "Default")
      (node (ref "Q26") (pin "B") (pinfunction "B_B") (pintype "passive"))
      (node (ref "R38") (pin "2") (pinfunction "2_2") (pintype "passive"))
    )
    (net (code "147") (name "Net-(Q27-PadB)") (class "Default")
      (node (ref "Q27") (pin "B") (pinfunction "B_B") (pintype "passive"))
      (node (ref "R39") (pin "2") (pinfunction "2_2") (pintype "passive"))
    )
    (net (code "148") (name "Net-(Q28-PadB)") (class "Default")
      (node (ref "Q28") (pin "B") (pinfunction "B_B") (pintype "passive"))
      (node (ref "R40") (pin "2") (pinfunction "2_2") (pintype "passive"))
    )
    (net (code "149") (name "Net-(Q29-PadB)") (class "Default")
      (node (ref "Q29") (pin "B") (pinfunction "B_B") (pintype "passive"))
      (node (ref "R41") (pin "2") (pinfunction "2_2") (pintype "passive"))
    )
    (net (code "150") (name "Net-(Q30-PadB)") (class "Default")
      (node (ref "Q30") (pin "B") (pinfunction "B_B") (pintype "passive"))
      (node (ref "R42") (pin "2") (pinfunction "2_2") (pintype "passive"))
    )
    (net (code "151") (name "Net-(Q31-PadB)") (class "Default")
      (node (ref "Q31") (pin "B") (pinfunction "B_B") (pintype "passive"))
      (node (ref "R43") (pin "2") (pinfunction "2_2") (pintype "passive"))
    )
    (net (code "152") (name "Net-(Q32-PadB)") (class "Default")
      (node (ref "Q32") (pin "B") (pinfunction "B_B") (pintype "passive"))
      (node (ref "R51") (pin "1") (pinfunction "1_1") (pintype "passive"))
    )
    (net (code "153") (name "Net-(Q33-PadB)") (class "Default")
      (node (ref "Q33") (pin "B") (pinfunction "B_B") (pintype "passive"))
      (node (ref "R49") (pin "1") (pinfunction "1_1") (pintype "passive"))
    )
    (net (code "154") (name "Net-(R13-Pad1)") (class "Default")
      (node (ref "R13") (pin "1") (pinfunction "1_1") (pintype "passive"))
      (node (ref "SJ5") (pin "2") (pinfunction "2_2") (pintype "passive"))
    )
    (net (code "155") (name "Net-(SK4A-S)") (class "Default")
      (node (ref "R31") (pin "1") (pinfunction "1_1") (pintype "passive"))
      (node (ref "SK4") (pin "1") (pinfunction "S_1") (pintype "passive"))
    )
    (net (code "156") (name "Net-(SK4B-S)") (class "Default")
      (node (ref "Q20") (pin "B") (pinfunction "B_B") (pintype "passive"))
      (node (ref "SK4") (pin "2") (pinfunction "S_2") (pintype "passive"))
    )
    (net (code "157") (name "Net-(SP1-2)") (class "Default")
      (node (ref "R8") (pin "2") (pinfunction "2_2") (pintype "passive"))
      (node (ref "SP1") (pin "+") (pinfunction "2_+") (pintype "passive"))
    )
    (net (code "158") (name "Net-(U2-PadNET)") (class "Default")
      (node (ref "U2") (pin "NET") (pinfunction "NET_NET") (pintype "bidirectional"))
      (node (ref "X3") (pin "1") (pinfunction "1_1") (pintype "passive"))
    )
    (net (code "159") (name "Net-(X6A-K)") (class "Default")
      (node (ref "Q10") (pin "C") (pinfunction "C_C") (pintype "passive"))
      (node (ref "Q11") (pin "C") (pinfunction "C_C") (pintype "passive"))
      (node (ref "X6") (pin "1") (pinfunction "K_1") (pintype "passive"))
    )
    (net (code "160") (name "Net-(X6B-K)") (class "Default")
      (node (ref "Q14") (pin "C") (pinfunction "C_C") (pintype "passive"))
      (node (ref "Q15") (pin "C") (pinfunction "C_C") (pintype "passive"))
      (node (ref "X6") (pin "2") (pinfunction "K_2") (pintype "passive"))
    )
    (net (code "161") (name "Net-(X7A-K)") (class "Default")
      (node (ref "R27") (pin "1") (pinfunction "1_1") (pintype "passive"))
      (node (ref "X7") (pin "1") (pinfunction "K_1") (pintype "passive"))
    )
    (net (code "162") (name "Net-(X7B-K)") (class "Default")
      (node (ref "R29") (pin "1") (pinfunction "1_1") (pintype "passive"))
      (node (ref "X7") (pin "2") (pinfunction "K_2") (pintype "passive"))
    )
    (net (code "163") (name "unconnected-(BT1B-AUDIO_OUT_P_L-Pad50)") (class "Default")
      (node (ref "BT1") (pin "50") (pinfunction "AUDIO_OUT_P_L_50") (pintype "output"))
    )
    (net (code "164") (name "unconnected-(BT1B-AUDIO_OUT_P_R-Pad47)") (class "Default")
      (node (ref "BT1") (pin "47") (pinfunction "AUDIO_OUT_P_R_47") (pintype "output"))
    )
    (net (code "165") (name "unconnected-(BT1H-~{RTS}-Pad20)") (class "Default")
      (node (ref "BT1") (pin "20") (pinfunction "~{RTS}_20") (pintype "output"))
    )
    (net (code "166") (name "unconnected-(JP3-Pad14)") (class "Default")
      (node (ref "JP3") (pin "14") (pinfunction "14_14") (pintype "passive"))
    )
    (net (code "167") (name "unconnected-(U1H-PD2-Pad54)") (class "Default")
      (node (ref "U1") (pin "54") (pinfunction "PD2_54") (pintype "bidirectional"))
    )
  )
)
